# salsa_II_v3b.net
KiCad netlist of a schematic drawn in EAGLE
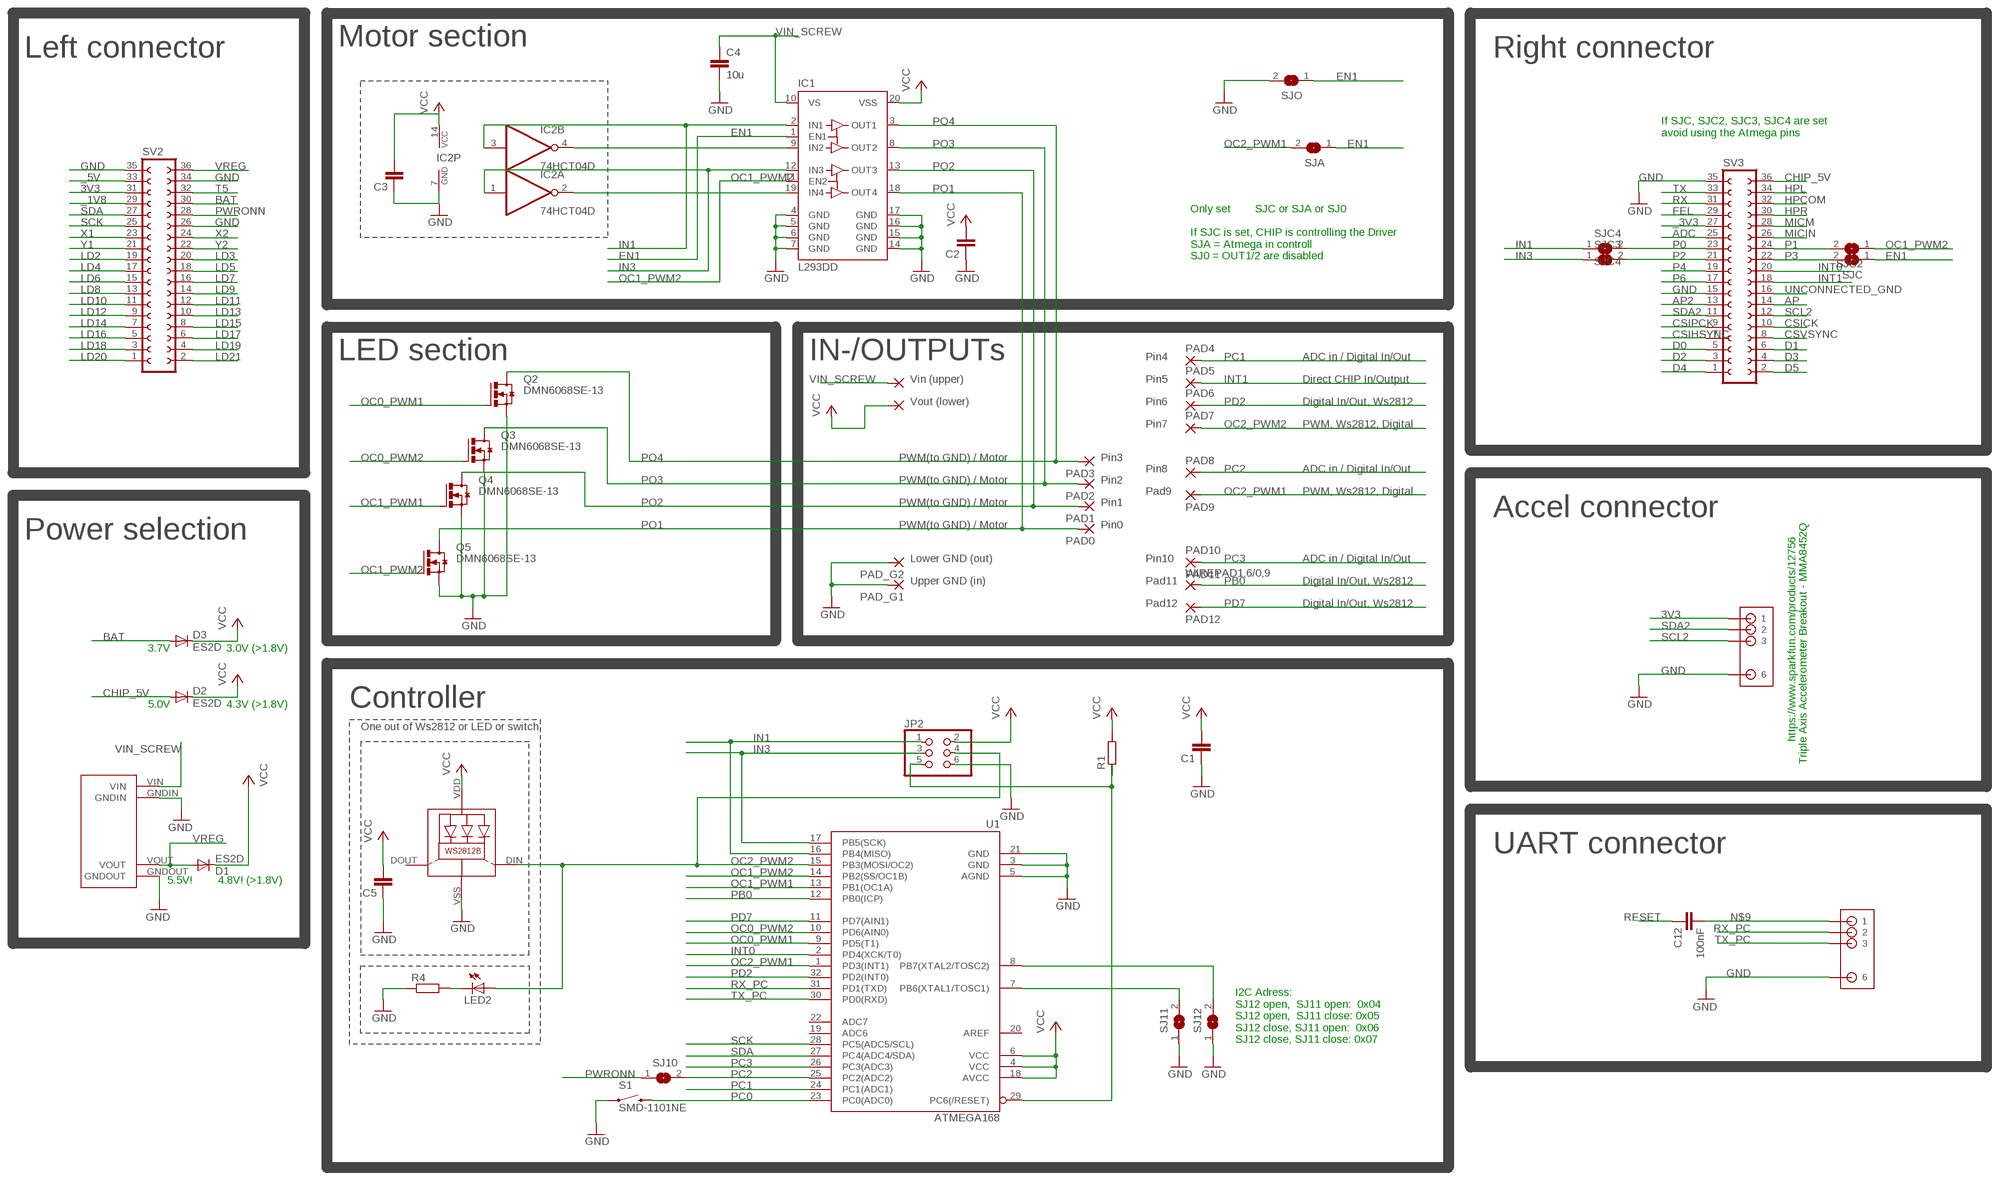
[diagram p0: schematic, sheet 1]

(export (version "E")
  (design (tool "Eeschema 10.0.6"))
  (components
    (comp (ref "C1")
      (value "C-EUC0805")
      (footprint "eagle-import:C0805")
      (libsource (lib "eagle-import") (part "C-EUC0805"))
    )
    (comp (ref "C2")
      (value "C-EUC0805")
      (footprint "eagle-import:C0805")
      (libsource (lib "eagle-import") (part "C-EUC0805"))
    )
    (comp (ref "C3")
      (value "C-EUC0805")
      (footprint "eagle-import:C0805")
      (libsource (lib "eagle-import") (part "C-EUC0805"))
    )
    (comp (ref "C4")
      (value "10u")
      (footprint "eagle-import:C1210")
      (libsource (lib "eagle-import") (part "C-EUC1210"))
    )
    (comp (ref "C5")
      (value "C-EUC0805")
      (footprint "eagle-import:C0805")
      (libsource (lib "eagle-import") (part "C-EUC0805"))
    )
    (comp (ref "C12")
      (value "100nF")
      (footprint "eagle-import:C1206")
      (libsource (lib "eagle-import") (part "C-EUC1206"))
    )
    (comp (ref "D1")
      (value "ES2D")
      (footprint "eagle-import:SMB")
      (libsource (lib "eagle-import") (part "ES2D"))
    )
    (comp (ref "D2")
      (value "ES2D")
      (footprint "eagle-import:SMB")
      (libsource (lib "eagle-import") (part "ES2D"))
    )
    (comp (ref "D3")
      (value "ES2D")
      (footprint "eagle-import:SMB")
      (libsource (lib "eagle-import") (part "ES2D"))
    )
    (comp (ref "IC1")
      (value "L293DD")
      (footprint "eagle-import:SO20")
      (libsource (lib "eagle-import") (part "L293DD"))
    )
    (comp (ref "IC2")
      (value "74HCT04D")
      (footprint "eagle-import:SO14")
      (libsource (lib "eagle-import") (part "7404DHCT"))
    )
    (comp (ref "JP2")
      (value "PINHD-2X3")
      (footprint "eagle-import:2X03")
      (libsource (lib "eagle-import") (part "PINHD-2X3"))
    )
    (comp (ref "LED1")
      (value "WS2812B")
      (footprint "eagle-import:WS2812B")
      (libsource (lib "eagle-import") (part "WS2812B"))
    )
    (comp (ref "LED2")
      (value "LEDCHIP-LED0805")
      (footprint "eagle-import:CHIP-LED0805")
      (libsource (lib "eagle-import") (part "LEDCHIP-LED0805"))
    )
    (comp (ref "PAD0")
      (value "3,17/1,3")
      (footprint "eagle-import:3,17_1,3")
      (libsource (lib "eagle-import") (part "3,17/1,3"))
    )
    (comp (ref "PAD1")
      (value "3,17/1,3")
      (footprint "eagle-import:3,17_1,3")
      (libsource (lib "eagle-import") (part "3,17/1,3"))
    )
    (comp (ref "PAD2")
      (value "3,17/1,3")
      (footprint "eagle-import:3,17_1,3")
      (libsource (lib "eagle-import") (part "3,17/1,3"))
    )
    (comp (ref "PAD3")
      (value "3,17/1,3")
      (footprint "eagle-import:3,17_1,3")
      (libsource (lib "eagle-import") (part "3,17/1,3"))
    )
    (comp (ref "PAD4")
      (value "3,17/1,3")
      (footprint "eagle-import:3,17_1,3")
      (libsource (lib "eagle-import") (part "3,17/1,3"))
    )
    (comp (ref "PAD5")
      (value "3,17/1,3")
      (footprint "eagle-import:3,17_1,3")
      (libsource (lib "eagle-import") (part "3,17/1,3"))
    )
    (comp (ref "PAD6")
      (value "3,17/1,3")
      (footprint "eagle-import:3,17_1,3")
      (libsource (lib "eagle-import") (part "3,17/1,3"))
    )
    (comp (ref "PAD7")
      (value "3,17/1,3")
      (footprint "eagle-import:3,17_1,3")
      (libsource (lib "eagle-import") (part "3,17/1,3"))
    )
    (comp (ref "PAD8")
      (value "3,17/1,3")
      (footprint "eagle-import:3,17_1,3")
      (libsource (lib "eagle-import") (part "3,17/1,3"))
    )
    (comp (ref "PAD9")
      (value "SMD2")
      (footprint "eagle-import:SMD1,27-2,54")
      (libsource (lib "eagle-import") (part "SMD2"))
    )
    (comp (ref "PAD10")
      (value "WIREPAD1,6/0,9")
      (footprint "eagle-import:1,6_0,9")
      (libsource (lib "eagle-import") (part "WIREPAD1,6/0,9"))
    )
    (comp (ref "PAD11")
      (value "WIREPADSMD1,27-254")
      (footprint "eagle-import:SMD1,27-2,54")
      (libsource (lib "eagle-import") (part "WIREPADSMD1,27-254"))
    )
    (comp (ref "PAD12")
      (value "SMD2")
      (footprint "eagle-import:SMD1,27-2,54")
      (libsource (lib "eagle-import") (part "SMD2"))
    )
    (comp (ref "PAD17")
      (value "3,17/1,3")
      (footprint "eagle-import:3,17_1,3")
      (libsource (lib "eagle-import") (part "3,17/1,3"))
    )
    (comp (ref "PAD_G1")
      (value "3,17/1,3")
      (footprint "eagle-import:3,17_1,3")
      (libsource (lib "eagle-import") (part "3,17/1,3"))
    )
    (comp (ref "PAD_G2")
      (value "3,17/1,3")
      (footprint "eagle-import:3,17_1,3")
      (libsource (lib "eagle-import") (part "3,17/1,3"))
    )
    (comp (ref "PAD_VIN")
      (value "3,17/1,3")
      (footprint "eagle-import:3,17_1,3")
      (libsource (lib "eagle-import") (part "3,17/1,3"))
    )
    (comp (ref "Q2")
      (value "DMN6068SE-13")
      (footprint "eagle-import:SOT223")
      (libsource (lib "eagle-import") (part "NMOSFET_SMD_223"))
    )
    (comp (ref "Q3")
      (value "DMN6068SE-13")
      (footprint "eagle-import:SOT223")
      (libsource (lib "eagle-import") (part "NMOSFET_SMD_223"))
    )
    (comp (ref "Q4")
      (value "DMN6068SE-13")
      (footprint "eagle-import:SOT223")
      (libsource (lib "eagle-import") (part "NMOSFET_SMD_223"))
    )
    (comp (ref "Q5")
      (value "DMN6068SE-13")
      (footprint "eagle-import:SOT223")
      (libsource (lib "eagle-import") (part "NMOSFET_SMD_223"))
    )
    (comp (ref "R1")
      (value "R-EU_M0805")
      (footprint "eagle-import:M0805")
      (libsource (lib "eagle-import") (part "R-EU_M0805"))
    )
    (comp (ref "R4")
      (value "R-EU_M1206")
      (footprint "eagle-import:M1206")
      (libsource (lib "eagle-import") (part "R-EU_M1206"))
    )
    (comp (ref "S1")
      (value "SMD-1101NE")
      (footprint "eagle-import:TACTILE-SWITCH-1101NE")
      (libsource (lib "eagle-import") (part "SWITCH-MOMENTARY-2-SMD-1101NE"))
    )
    (comp (ref "SJ10")
      (value "SJ")
      (footprint "eagle-import:SJ")
      (libsource (lib "eagle-import") (part "SJ"))
    )
    (comp (ref "SJ11")
      (value "SJ")
      (footprint "eagle-import:SJ")
      (libsource (lib "eagle-import") (part "SJ"))
    )
    (comp (ref "SJ12")
      (value "SJ")
      (footprint "eagle-import:SJ")
      (libsource (lib "eagle-import") (part "SJ"))
    )
    (comp (ref "SJA") (value "SJ") (footprint "eagle-import:SJ") (libsource (lib "eagle-import") (part "SJ")))
    (comp (ref "SJC") (value "SJ") (footprint "eagle-import:SJ") (libsource (lib "eagle-import") (part "SJ")))
    (comp (ref "SJC2")
      (value "SJ")
      (footprint "eagle-import:SJ")
      (libsource (lib "eagle-import") (part "SJ"))
    )
    (comp (ref "SJC3")
      (value "SJ")
      (footprint "eagle-import:SJ")
      (libsource (lib "eagle-import") (part "SJ"))
    )
    (comp (ref "SJC4")
      (value "SJC4")
      (footprint "eagle-import:SJ")
      (libsource (lib "eagle-import") (part "SJ"))
    )
    (comp (ref "SJO") (value "SJ") (footprint "eagle-import:SJ") (libsource (lib "eagle-import") (part "SJ")))
    (comp (ref "SV2")
      (value "FE18-2")
      (footprint "eagle-import:FE18-2")
      (libsource (lib "eagle-import") (part "FE18-2"))
    )
    (comp (ref "SV3")
      (value "FE18-2")
      (footprint "eagle-import:FE18-2")
      (libsource (lib "eagle-import") (part "FE18-2"))
    )
    (comp (ref "U$1")
      (value "MP1584EN")
      (footprint "eagle-import:MP1584EN")
      (libsource (lib "eagle-import") (part "MP1584EN"))
    )
    (comp (ref "U$3")
      (value "6_TO_4_HEADER")
      (footprint "eagle-import:6_TO_4_HEADER")
      (libsource (lib "eagle-import") (part "6_TO_4_HEADER"))
    )
    (comp (ref "U$4")
      (value "6_TO_4_HEADER")
      (footprint "eagle-import:6_TO_4_HEADER")
      (libsource (lib "eagle-import") (part "6_TO_4_HEADER"))
    )
    (comp (ref "U1")
      (value "ATMEGA168")
      (footprint "eagle-import:TQFP32-08")
      (libsource (lib "eagle-import") (part "ATMEGA168"))
    )
  )
  (nets
    (net (code "1") (name "/3V3") (class "Default")
      (node (ref "SV2") (pin "31") (pinfunction "31_31") (pintype "passive"))
      (node (ref "U$4") (pin "1") (pinfunction "1_1") (pintype "bidirectional"))
    )
    (net (code "2") (name "/ADC") (class "Default")
      (node (ref "SV3") (pin "25") (pinfunction "25_25") (pintype "passive"))
    )
    (net (code "3") (name "/AP") (class "Default")
      (node (ref "SV3") (pin "14") (pinfunction "14_14") (pintype "passive"))
    )
    (net (code "4") (name "/AP2") (class "Default")
      (node (ref "SV3") (pin "13") (pinfunction "13_13") (pintype "passive"))
    )
    (net (code "5") (name "/BAT") (class "Default")
      (node (ref "D3") (pin "A") (pinfunction "A_A") (pintype "passive"))
      (node (ref "SV2") (pin "30") (pinfunction "30_30") (pintype "passive"))
    )
    (net (code "6") (name "/CHIP_5V") (class "Default")
      (node (ref "D2") (pin "A") (pinfunction "A_A") (pintype "passive"))
      (node (ref "SV3") (pin "36") (pinfunction "36_36") (pintype "passive"))
    )
    (net (code "7") (name "/CSICK") (class "Default")
      (node (ref "SV3") (pin "10") (pinfunction "10_10") (pintype "passive"))
    )
    (net (code "8") (name "/CSIHSYNC") (class "Default")
      (node (ref "SV3") (pin "7") (pinfunction "7_7") (pintype "passive"))
    )
    (net (code "9") (name "/CSIPCK") (class "Default")
      (node (ref "SV3") (pin "9") (pinfunction "9_9") (pintype "passive"))
    )
    (net (code "10") (name "/CSVSYNC") (class "Default")
      (node (ref "SV3") (pin "8") (pinfunction "8_8") (pintype "passive"))
    )
    (net (code "11") (name "/D0") (class "Default")
      (node (ref "SV3") (pin "5") (pinfunction "5_5") (pintype "passive"))
    )
    (net (code "12") (name "/D1") (class "Default")
      (node (ref "SV3") (pin "6") (pinfunction "6_6") (pintype "passive"))
    )
    (net (code "13") (name "/D2") (class "Default")
      (node (ref "SV3") (pin "3") (pinfunction "3_3") (pintype "passive"))
    )
    (net (code "14") (name "/D3") (class "Default")
      (node (ref "SV3") (pin "4") (pinfunction "4_4") (pintype "passive"))
    )
    (net (code "15") (name "/D4") (class "Default")
      (node (ref "SV3") (pin "1") (pinfunction "1_1") (pintype "passive"))
    )
    (net (code "16") (name "/D5") (class "Default")
      (node (ref "SV3") (pin "2") (pinfunction "2_2") (pintype "passive"))
    )
    (net (code "17") (name "/EN1") (class "Default")
      (node (ref "IC1") (pin "1") (pinfunction "EN1_1") (pintype "input"))
      (node (ref "SJA") (pin "1") (pinfunction "1_1") (pintype "passive"))
      (node (ref "SJC") (pin "1") (pinfunction "1_1") (pintype "passive"))
      (node (ref "SJO") (pin "1") (pinfunction "1_1") (pintype "passive"))
    )
    (net (code "18") (name "/FEL") (class "Default")
      (node (ref "SV3") (pin "29") (pinfunction "29_29") (pintype "passive"))
    )
    (net (code "19") (name "/HPCOM") (class "Default")
      (node (ref "SV3") (pin "32") (pinfunction "32_32") (pintype "passive"))
    )
    (net (code "20") (name "/HPL") (class "Default")
      (node (ref "SV3") (pin "34") (pinfunction "34_34") (pintype "passive"))
    )
    (net (code "21") (name "/HPR") (class "Default")
      (node (ref "SV3") (pin "30") (pinfunction "30_30") (pintype "passive"))
    )
    (net (code "22") (name "/IN1") (class "Default")
      (node (ref "IC1") (pin "2") (pinfunction "IN1_2") (pintype "input"))
      (node (ref "IC2") (pin "3") (pinfunction "I_3") (pintype "input"))
      (node (ref "JP2") (pin "1") (pinfunction "1_1") (pintype "passive"))
      (node (ref "SJC4") (pin "1") (pinfunction "1_1") (pintype "passive"))
      (node (ref "U1") (pin "16") (pinfunction "PB4(MISO)_16") (pintype "bidirectional"))
    )
    (net (code "23") (name "/IN3") (class "Default")
      (node (ref "IC1") (pin "12") (pinfunction "IN3_12") (pintype "input"))
      (node (ref "IC2") (pin "1") (pinfunction "I_1") (pintype "input"))
      (node (ref "JP2") (pin "3") (pinfunction "3_3") (pintype "passive"))
      (node (ref "SJC3") (pin "1") (pinfunction "1_1") (pintype "passive"))
      (node (ref "U1") (pin "17") (pinfunction "PB5(SCK)_17") (pintype "bidirectional"))
    )
    (net (code "24") (name "/INT0") (class "Default")
      (node (ref "SV3") (pin "20") (pinfunction "20_20") (pintype "passive"))
      (node (ref "U1") (pin "2") (pinfunction "PD4(XCK/T0)_2") (pintype "bidirectional"))
    )
    (net (code "25") (name "/INT1") (class "Default")
      (node (ref "PAD5") (pin "1") (pinfunction "P_1") (pintype "passive"))
      (node (ref "SV3") (pin "18") (pinfunction "18_18") (pintype "passive"))
    )
    (net (code "26") (name "/LD2") (class "Default")
      (node (ref "SV2") (pin "19") (pinfunction "19_19") (pintype "passive"))
    )
    (net (code "27") (name "/LD3") (class "Default")
      (node (ref "SV2") (pin "20") (pinfunction "20_20") (pintype "passive"))
    )
    (net (code "28") (name "/LD4") (class "Default")
      (node (ref "SV2") (pin "17") (pinfunction "17_17") (pintype "passive"))
    )
    (net (code "29") (name "/LD5") (class "Default")
      (node (ref "SV2") (pin "18") (pinfunction "18_18") (pintype "passive"))
    )
    (net (code "30") (name "/LD6") (class "Default")
      (node (ref "SV2") (pin "15") (pinfunction "15_15") (pintype "passive"))
    )
    (net (code "31") (name "/LD7") (class "Default")
      (node (ref "SV2") (pin "16") (pinfunction "16_16") (pintype "passive"))
    )
    (net (code "32") (name "/LD8") (class "Default")
      (node (ref "SV2") (pin "13") (pinfunction "13_13") (pintype "passive"))
    )
    (net (code "33") (name "/LD9") (class "Default")
      (node (ref "SV2") (pin "14") (pinfunction "14_14") (pintype "passive"))
    )
    (net (code "34") (name "/LD10") (class "Default")
      (node (ref "SV2") (pin "11") (pinfunction "11_11") (pintype "passive"))
    )
    (net (code "35") (name "/LD11") (class "Default")
      (node (ref "SV2") (pin "12") (pinfunction "12_12") (pintype "passive"))
    )
    (net (code "36") (name "/LD12") (class "Default")
      (node (ref "SV2") (pin "9") (pinfunction "9_9") (pintype "passive"))
    )
    (net (code "37") (name "/LD13") (class "Default")
      (node (ref "SV2") (pin "10") (pinfunction "10_10") (pintype "passive"))
    )
    (net (code "38") (name "/LD14") (class "Default")
      (node (ref "SV2") (pin "7") (pinfunction "7_7") (pintype "passive"))
    )
    (net (code "39") (name "/LD15") (class "Default")
      (node (ref "SV2") (pin "8") (pinfunction "8_8") (pintype "passive"))
    )
    (net (code "40") (name "/LD16") (class "Default")
      (node (ref "SV2") (pin "5") (pinfunction "5_5") (pintype "passive"))
    )
    (net (code "41") (name "/LD17") (class "Default")
      (node (ref "SV2") (pin "6") (pinfunction "6_6") (pintype "passive"))
    )
    (net (code "42") (name "/LD18") (class "Default")
      (node (ref "SV2") (pin "3") (pinfunction "3_3") (pintype "passive"))
    )
    (net (code "43") (name "/LD19") (class "Default")
      (node (ref "SV2") (pin "4") (pinfunction "4_4") (pintype "passive"))
    )
    (net (code "44") (name "/LD20") (class "Default")
      (node (ref "SV2") (pin "1") (pinfunction "1_1") (pintype "passive"))
    )
    (net (code "45") (name "/LD21") (class "Default")
      (node (ref "SV2") (pin "2") (pinfunction "2_2") (pintype "passive"))
    )
    (net (code "46") (name "/MICIN") (class "Default")
      (node (ref "SV3") (pin "26") (pinfunction "26_26") (pintype "passive"))
    )
    (net (code "47") (name "/MICM") (class "Default")
      (node (ref "SV3") (pin "28") (pinfunction "28_28") (pintype "passive"))
    )
    (net (code "48") (name "/N$9") (class "Default")
      (node (ref "C12") (pin "2") (pinfunction "2_2") (pintype "passive"))
      (node (ref "U$3") (pin "1") (pinfunction "1_1") (pintype "bidirectional"))
    )
    (net (code "49") (name "/OC0_PWM1") (class "Default")
      (node (ref "Q2") (pin "1") (pinfunction "G_1") (pintype "passive"))
      (node (ref "U1") (pin "9") (pinfunction "PD5(T1)_9") (pintype "bidirectional"))
    )
    (net (code "50") (name "/OC0_PWM2") (class "Default")
      (node (ref "Q3") (pin "1") (pinfunction "G_1") (pintype "passive"))
      (node (ref "U1") (pin "10") (pinfunction "PD6(AIN0)_10") (pintype "bidirectional"))
    )
    (net (code "51") (name "/OC1_PWM1") (class "Default")
      (node (ref "Q4") (pin "1") (pinfunction "G_1") (pintype "passive"))
      (node (ref "U1") (pin "13") (pinfunction "PB1(OC1A)_13") (pintype "bidirectional"))
    )
    (net (code "52") (name "/OC1_PWM2") (class "Default")
      (node (ref "IC1") (pin "11") (pinfunction "EN2_11") (pintype "input"))
      (node (ref "Q5") (pin "1") (pinfunction "G_1") (pintype "passive"))
      (node (ref "SJC2") (pin "1") (pinfunction "1_1") (pintype "passive"))
      (node (ref "U1") (pin "14") (pinfunction "PB2(SS/OC1B)_14") (pintype "bidirectional"))
    )
    (net (code "53") (name "/OC2_PWM1") (class "Default")
      (node (ref "PAD9") (pin "1") (pinfunction "P_1") (pintype "passive"))
      (node (ref "SJA") (pin "2") (pinfunction "2_2") (pintype "passive"))
      (node (ref "U1") (pin "1") (pinfunction "PD3(INT1)_1") (pintype "bidirectional"))
    )
    (net (code "54") (name "/OC2_PWM2") (class "Default")
      (node (ref "JP2") (pin "4") (pinfunction "4_4") (pintype "passive"))
      (node (ref "LED1") (pin "DIN") (pinfunction "DI_DIN") (pintype "input"))
      (node (ref "LED2") (pin "A") (pinfunction "A_A") (pintype "passive"))
      (node (ref "PAD7") (pin "1") (pinfunction "P_1") (pintype "passive"))
      (node (ref "U1") (pin "15") (pinfunction "PB3(MOSI/OC2)_15") (pintype "bidirectional"))
    )
    (net (code "55") (name "/P0") (class "Default")
      (node (ref "SJC4") (pin "2") (pinfunction "2_2") (pintype "passive"))
      (node (ref "SV3") (pin "23") (pinfunction "23_23") (pintype "passive"))
    )
    (net (code "56") (name "/P1") (class "Default")
      (node (ref "SJC2") (pin "2") (pinfunction "2_2") (pintype "passive"))
      (node (ref "SV3") (pin "24") (pinfunction "24_24") (pintype "passive"))
    )
    (net (code "57") (name "/P2") (class "Default")
      (node (ref "SJC3") (pin "2") (pinfunction "2_2") (pintype "passive"))
      (node (ref "SV3") (pin "21") (pinfunction "21_21") (pintype "passive"))
    )
    (net (code "58") (name "/P3") (class "Default")
      (node (ref "SJC") (pin "2") (pinfunction "2_2") (pintype "passive"))
      (node (ref "SV3") (pin "22") (pinfunction "22_22") (pintype "passive"))
    )
    (net (code "59") (name "/P4") (class "Default")
      (node (ref "SV3") (pin "19") (pinfunction "19_19") (pintype "passive"))
    )
    (net (code "60") (name "/P6") (class "Default")
      (node (ref "SV3") (pin "17") (pinfunction "17_17") (pintype "passive"))
    )
    (net (code "61") (name "/PB0") (class "Default")
      (node (ref "PAD11") (pin "1") (pinfunction "P_1") (pintype "passive"))
      (node (ref "U1") (pin "12") (pinfunction "PB0(ICP)_12") (pintype "bidirectional"))
    )
    (net (code "62") (name "/PC0") (class "Default")
      (node (ref "S1") (pin "P$2") (pinfunction "2_P$2") (pintype "passive"))
      (node (ref "U1") (pin "23") (pinfunction "PC0(ADC0)_23") (pintype "bidirectional"))
    )
    (net (code "63") (name "/PC1") (class "Default")
      (node (ref "PAD4") (pin "1") (pinfunction "P_1") (pintype "passive"))
      (node (ref "U1") (pin "24") (pinfunction "PC1(ADC1)_24") (pintype "bidirectional"))
    )
    (net (code "64") (name "/PC2") (class "Default")
      (node (ref "PAD8") (pin "1") (pinfunction "P_1") (pintype "passive"))
      (node (ref "SJ10") (pin "2") (pinfunction "2_2") (pintype "passive"))
      (node (ref "U1") (pin "25") (pinfunction "PC2(ADC2)_25") (pintype "bidirectional"))
    )
    (net (code "65") (name "/PC3") (class "Default")
      (node (ref "PAD10") (pin "1") (pinfunction "P_1") (pintype "passive"))
      (node (ref "U1") (pin "26") (pinfunction "PC3(ADC3)_26") (pintype "bidirectional"))
    )
    (net (code "66") (name "/PD2") (class "Default")
      (node (ref "PAD6") (pin "1") (pinfunction "P_1") (pintype "passive"))
      (node (ref "U1") (pin "32") (pinfunction "PD2(INT0)_32") (pintype "bidirectional"))
    )
    (net (code "67") (name "/PD7") (class "Default")
      (node (ref "PAD12") (pin "1") (pinfunction "P_1") (pintype "passive"))
      (node (ref "U1") (pin "11") (pinfunction "PD7(AIN1)_11") (pintype "bidirectional"))
    )
    (net (code "68") (name "/PO1") (class "Default")
      (node (ref "IC1") (pin "18") (pinfunction "OUT4_18") (pintype "output"))
      (node (ref "PAD0") (pin "1") (pinfunction "P_1") (pintype "passive"))
      (node (ref "Q5") (pin "2") (pinfunction "D_2") (pintype "passive"))
      (node (ref "Q5") (pin "4") (pinfunction "D_4") (pintype "passive"))
    )
    (net (code "69") (name "/PO2") (class "Default")
      (node (ref "IC1") (pin "13") (pinfunction "OUT3_13") (pintype "output"))
      (node (ref "PAD1") (pin "1") (pinfunction "P_1") (pintype "passive"))
      (node (ref "Q4") (pin "2") (pinfunction "D_2") (pintype "passive"))
      (node (ref "Q4") (pin "4") (pinfunction "D_4") (pintype "passive"))
    )
    (net (code "70") (name "/PO3") (class "Default")
      (node (ref "IC1") (pin "8") (pinfunction "OUT2_8") (pintype "output"))
      (node (ref "PAD2") (pin "1") (pinfunction "P_1") (pintype "passive"))
      (node (ref "Q3") (pin "2") (pinfunction "D_2") (pintype "passive"))
      (node (ref "Q3") (pin "4") (pinfunction "D_4") (pintype "passive"))
    )
    (net (code "71") (name "/PO4") (class "Default")
      (node (ref "IC1") (pin "3") (pinfunction "OUT1_3") (pintype "output"))
      (node (ref "PAD3") (pin "1") (pinfunction "P_1") (pintype "passive"))
      (node (ref "Q2") (pin "2") (pinfunction "D_2") (pintype "passive"))
      (node (ref "Q2") (pin "4") (pinfunction "D_4") (pintype "passive"))
    )
    (net (code "72") (name "/PWRONN") (class "Default")
      (node (ref "SJ10") (pin "1") (pinfunction "1_1") (pintype "passive"))
      (node (ref "SV2") (pin "28") (pinfunction "28_28") (pintype "passive"))
    )
    (net (code "73") (name "/RESET") (class "Default")
      (node (ref "C12") (pin "1") (pinfunction "1_1") (pintype "passive"))
      (node (ref "JP2") (pin "5") (pinfunction "5_5") (pintype "passive"))
      (node (ref "R1") (pin "1") (pinfunction "1_1") (pintype "passive"))
      (node (ref "U1") (pin "29") (pinfunction "PC6(/RESET)_29") (pintype "bidirectional"))
    )
    (net (code "74") (name "/RX") (class "Default")
      (node (ref "SV3") (pin "31") (pinfunction "31_31") (pintype "passive"))
    )
    (net (code "75") (name "/RX_PC") (class "Default")
      (node (ref "U$3") (pin "2") (pinfunction "2_2") (pintype "bidirectional"))
      (node (ref "U1") (pin "31") (pinfunction "PD1(TXD)_31") (pintype "bidirectional"))
    )
    (net (code "76") (name "/SCK") (class "Default")
      (node (ref "SV2") (pin "25") (pinfunction "25_25") (pintype "passive"))
      (node (ref "U1") (pin "28") (pinfunction "PC5(ADC5/SCL)_28") (pintype "bidirectional"))
    )
    (net (code "77") (name "/SCL2") (class "Default")
      (node (ref "SV3") (pin "12") (pinfunction "12_12") (pintype "passive"))
      (node (ref "U$4") (pin "3") (pinfunction "3_3") (pintype "bidirectional"))
    )
    (net (code "78") (name "/SDA") (class "Default")
      (node (ref "SV2") (pin "27") (pinfunction "27_27") (pintype "passive"))
      (node (ref "U1") (pin "27") (pinfunction "PC4(ADC4/SDA)_27") (pintype "bidirectional"))
    )
    (net (code "79") (name "/SDA2") (class "Default")
      (node (ref "SV3") (pin "11") (pinfunction "11_11") (pintype "passive"))
      (node (ref "U$4") (pin "2") (pinfunction "2_2") (pintype "bidirectional"))
    )
    (net (code "80") (name "/T5") (class "Default")
      (node (ref "SV2") (pin "32") (pinfunction "32_32") (pintype "passive"))
    )
    (net (code "81") (name "/TX") (class "Default")
      (node (ref "SV3") (pin "33") (pinfunction "33_33") (pintype "passive"))
    )
    (net (code "82") (name "/TX_PC") (class "Default")
      (node (ref "U$3") (pin "3") (pinfunction "3_3") (pintype "bidirectional"))
      (node (ref "U1") (pin "30") (pinfunction "PD0(RXD)_30") (pintype "bidirectional"))
    )
    (net (code "83") (name "/UNCONNECTED_GND") (class "Default")
      (node (ref "SV3") (pin "16") (pinfunction "16_16") (pintype "passive"))
    )
    (net (code "84") (name "/VIN_SCREW") (class "Default")
      (node (ref "C4") (pin "1") (pinfunction "1_1") (pintype "passive"))
      (node (ref "IC1") (pin "10") (pinfunction "VS_10") (pintype "power_in"))
      (node (ref "PAD_VIN") (pin "1") (pinfunction "P_1") (pintype "passive"))
      (node (ref "U$1") (pin "VIN") (pinfunction "VIN_VIN") (pintype "power_in"))
    )
    (net (code "85") (name "/VREG") (class "Default")
      (node (ref "D1") (pin "A") (pinfunction "A_A") (pintype "passive"))
      (node (ref "SV2") (pin "36") (pinfunction "36_36") (pintype "passive"))
      (node (ref "U$1") (pin "VOUT") (pinfunction "VOUT_VOUT") (pintype "power_in"))
    )
    (net (code "86") (name "/X1") (class "Default")
      (node (ref "SV2") (pin "23") (pinfunction "23_23") (pintype "passive"))
    )
    (net (code "87") (name "/X2") (class "Default")
      (node (ref "SV2") (pin "24") (pinfunction "24_24") (pintype "passive"))
    )
    (net (code "88") (name "/Y1") (class "Default")
      (node (ref "SV2") (pin "21") (pinfunction "21_21") (pintype "passive"))
    )
    (net (code "89") (name "/Y2") (class "Default")
      (node (ref "SV2") (pin "22") (pinfunction "22_22") (pintype "passive"))
    )
    (net (code "90") (name "/_1V8") (class "Default")
      (node (ref "SV2") (pin "29") (pinfunction "29_29") (pintype "passive"))
    )
    (net (code "91") (name "/_3V3") (class "Default")
      (node (ref "SV3") (pin "27") (pinfunction "27_27") (pintype "passive"))
    )
    (net (code "92") (name "/_5V") (class "Default")
      (node (ref "SV2") (pin "33") (pinfunction "33_33") (pintype "passive"))
    )
    (net (code "93") (name "GND") (class "Default")
      (node (ref "C1") (pin "1") (pinfunction "1_1") (pintype "passive"))
      (node (ref "C2") (pin "1") (pinfunction "1_1") (pintype "passive"))
      (node (ref "C3") (pin "1") (pinfunction "1_1") (pintype "passive"))
      (node (ref "C4") (pin "2") (pinfunction "2_2") (pintype "passive"))
      (node (ref "C5") (pin "1") (pinfunction "1_1") (pintype "passive"))
      (node (ref "IC1") (pin "14") (pinfunction "GND_14") (pintype "power_in"))
      (node (ref "IC1") (pin "15") (pinfunction "GND_15") (pintype "power_in"))
      (node (ref "IC1") (pin "16") (pinfunction "GND_16") (pintype "power_in"))
      (node (ref "IC1") (pin "17") (pinfunction "GND_17") (pintype "power_in"))
      (node (ref "IC1") (pin "4") (pinfunction "GND_4") (pintype "power_in"))
      (node (ref "IC1") (pin "5") (pinfunction "GND_5") (pintype "power_in"))
      (node (ref "IC1") (pin "6") (pinfunction "GND_6") (pintype "power_in"))
      (node (ref "IC1") (pin "7") (pinfunction "GND_7") (pintype "power_in"))
      (node (ref "IC2") (pin "7") (pinfunction "GND_7") (pintype "power_in"))
      (node (ref "JP2") (pin "6") (pinfunction "6_6") (pintype "passive"))
      (node (ref "LED1") (pin "VSS") (pinfunction "GND_VSS") (pintype "power_in"))
      (node (ref "PAD_G1") (pin "1") (pinfunction "P_1") (pintype "passive"))
      (node (ref "PAD_G2") (pin "1") (pinfunction "P_1") (pintype "passive"))
      (node (ref "Q2") (pin "3") (pinfunction "S_3") (pintype "passive"))
      (node (ref "Q3") (pin "3") (pinfunction "S_3") (pintype "passive"))
      (node (ref "Q4") (pin "3") (pinfunction "S_3") (pintype "passive"))
      (node (ref "Q5") (pin "3") (pinfunction "S_3") (pintype "passive"))
      (node (ref "R4") (pin "1") (pinfunction "1_1") (pintype "passive"))
      (node (ref "S1") (pin "P$1") (pinfunction "1_P$1") (pintype "passive"))
      (node (ref "SJ11") (pin "1") (pinfunction "1_1") (pintype "passive"))
      (node (ref "SJ12") (pin "1") (pinfunction "1_1") (pintype "passive"))
      (node (ref "SJO") (pin "2") (pinfunction "2_2") (pintype "passive"))
      (node (ref "SV2") (pin "26") (pinfunction "26_26") (pintype "passive"))
      (node (ref "SV2") (pin "34") (pinfunction "34_34") (pintype "passive"))
      (node (ref "SV2") (pin "35") (pinfunction "35_35") (pintype "passive"))
      (node (ref "SV3") (pin "15") (pinfunction "15_15") (pintype "passive"))
      (node (ref "SV3") (pin "35") (pinfunction "35_35") (pintype "passive"))
      (node (ref "U$1") (pin "GNDIN") (pinfunction "GNDIN_GNDIN") (pintype "power_in"))
      (node (ref "U$1") (pin "GNDOUT") (pinfunction "GNDOUT_GNDOUT") (pintype "power_in"))
      (node (ref "U$3") (pin "6") (pinfunction "6_6") (pintype "bidirectional"))
      (node (ref "U$4") (pin "6") (pinfunction "6_6") (pintype "bidirectional"))
      (node (ref "U1") (pin "21") (pinfunction "GND_21") (pintype "bidirectional"))
      (node (ref "U1") (pin "3") (pinfunction "GND_3") (pintype "bidirectional"))
      (node (ref "U1") (pin "5") (pinfunction "AGND_5") (pintype "bidirectional"))
    )
    (net (code "94") (name "Net-(IC1-IN2)") (class "Default")
      (node (ref "IC1") (pin "9") (pinfunction "IN2_9") (pintype "input"))
      (node (ref "IC2") (pin "4") (pinfunction "O_4") (pintype "output"))
    )
    (net (code "95") (name "Net-(IC1-IN4)") (class "Default")
      (node (ref "IC1") (pin "19") (pinfunction "IN4_19") (pintype "input"))
      (node (ref "IC2") (pin "2") (pinfunction "O_2") (pintype "output"))
    )
    (net (code "96") (name "Net-(LED2-PadC)") (class "Default")
      (node (ref "LED2") (pin "C") (pinfunction "C_C") (pintype "passive"))
      (node (ref "R4") (pin "2") (pinfunction "2_2") (pintype "passive"))
    )
    (net (code "97") (name "Net-(U1-PB6(XTAL1{slash}TOSC1))") (class "Default")
      (node (ref "SJ11") (pin "2") (pinfunction "2_2") (pintype "passive"))
      (node (ref "U1") (pin "7") (pinfunction "PB6(XTAL1/TOSC1)_7") (pintype "bidirectional"))
    )
    (net (code "98") (name "Net-(U1-PB7(XTAL2{slash}TOSC2))") (class "Default")
      (node (ref "SJ12") (pin "2") (pinfunction "2_2") (pintype "passive"))
      (node (ref "U1") (pin "8") (pinfunction "PB7(XTAL2/TOSC2)_8") (pintype "bidirectional"))
    )
    (net (code "99") (name "VCC") (class "Default")
      (node (ref "C1") (pin "2") (pinfunction "2_2") (pintype "passive"))
      (node (ref "C2") (pin "2") (pinfunction "2_2") (pintype "passive"))
      (node (ref "C3") (pin "2") (pinfunction "2_2") (pintype "passive"))
      (node (ref "C5") (pin "2") (pinfunction "2_2") (pintype "passive"))
      (node (ref "D1") (pin "C") (pinfunction "C_C") (pintype "passive"))
      (node (ref "D2") (pin "C") (pinfunction "C_C") (pintype "passive"))
      (node (ref "D3") (pin "C") (pinfunction "C_C") (pintype "passive"))
      (node (ref "IC1") (pin "20") (pinfunction "VSS_20") (pintype "power_in"))
      (node (ref "IC2") (pin "14") (pinfunction "VCC_14") (pintype "power_in"))
      (node (ref "JP2") (pin "2") (pinfunction "2_2") (pintype "passive"))
      (node (ref "LED1") (pin "VDD") (pinfunction "VDD_VDD") (pintype "power_in"))
      (node (ref "PAD17") (pin "1") (pinfunction "P_1") (pintype "passive"))
      (node (ref "R1") (pin "2") (pinfunction "2_2") (pintype "passive"))
      (node (ref "U1") (pin "18") (pinfunction "AVCC_18") (pintype "bidirectional"))
      (node (ref "U1") (pin "4") (pinfunction "VCC_4") (pintype "bidirectional"))
      (node (ref "U1") (pin "6") (pinfunction "VCC_6") (pintype "bidirectional"))
    )
    (net (code "100") (name "unconnected-(LED1-DO-PadDOUT)") (class "Default")
      (node (ref "LED1") (pin "DOUT") (pinfunction "DO_DOUT") (pintype "output"))
    )
    (net (code "101") (name "unconnected-(U1-ADC6-Pad19)") (class "Default")
      (node (ref "U1") (pin "19") (pinfunction "ADC6_19") (pintype "bidirectional"))
    )
    (net (code "102") (name "unconnected-(U1-ADC7-Pad22)") (class "Default")
      (node (ref "U1") (pin "22") (pinfunction "ADC7_22") (pintype "bidirectional"))
    )
    (net (code "103") (name "unconnected-(U1-AREF-Pad20)") (class "Default")
      (node (ref "U1") (pin "20") (pinfunction "AREF_20") (pintype "bidirectional"))
    )
  )
)
